# Sheet1.net
KiCad netlist of a schematic drawn in Altium Designer
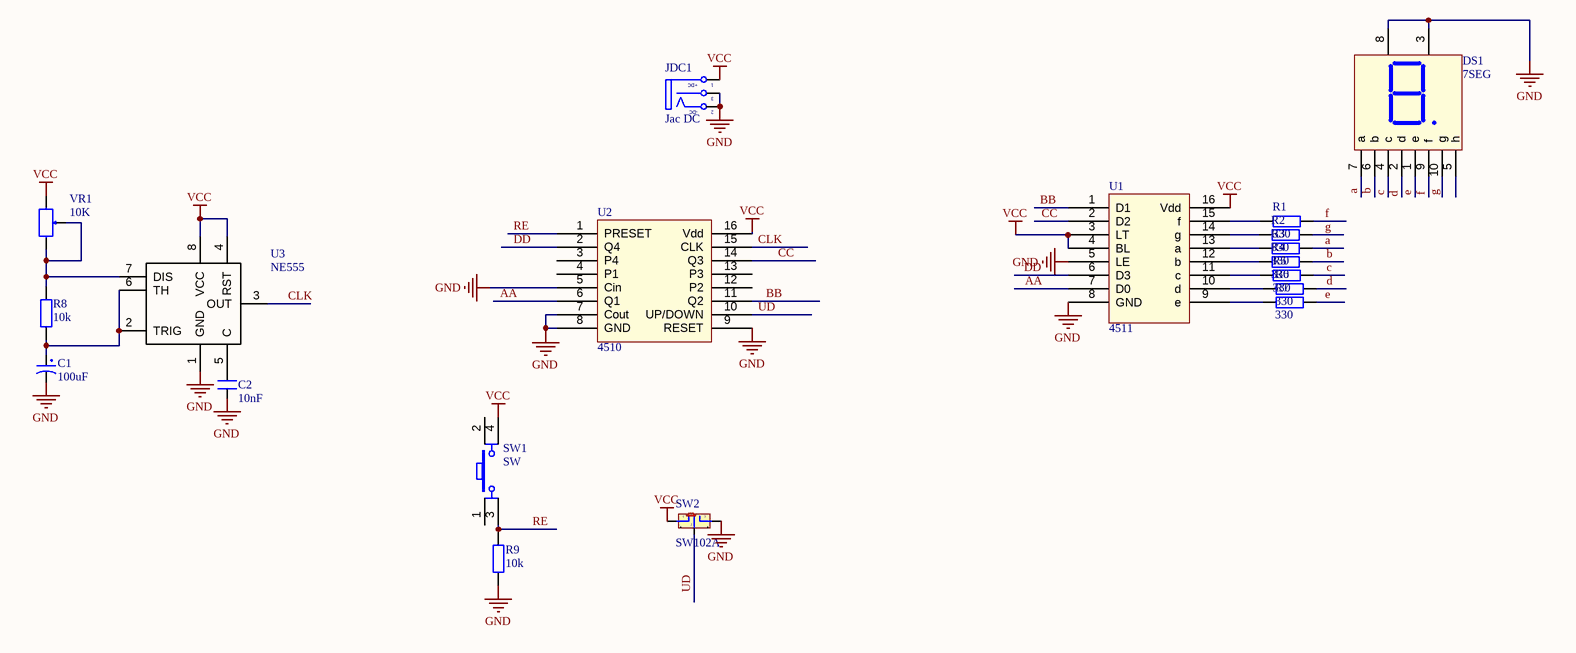
[diagram p0: Sheet1.SchDoc]

(export (version "E")
  (design (tool "Eeschema 10.0.6"))
  (components
    (comp (ref "C1")
      (value "100uF")
      (footprint "CP1/2")
      (description "Cap P  0,1uF < 22uF , 16 - 50V")
      (libsource (lib "syhaunguyen") (part "CP1"))
    )
    (comp (ref "C2")
      (value "10nF")
      (footprint "CN1")
      (description "Cap np  1pF - 472pF")
      (libsource (lib "syhaunguyen") (part "CN1"))
    )
    (comp (ref "DS1")
      (value "7SEG")
      (footprint "LED7SEG-1-0.56")
      (description "14.2 mm General Purpose Blue 7-Segment Display: CC, RH DP, Gray Surface")
      (fields (field (name "PUBLISHER") "Altium Limited"))
      (libsource (lib "LIBRARY") (part "LED7SEG-1"))
    )
    (comp (ref "JDC1")
      (value "Jac DC")
      (footprint "DC-IN")
      (description "Jac DC input")
      (libsource (lib "syhaunguyen") (part "DCIN"))
    )
    (comp (ref "R1")
      (value "330")
      (footprint "R1/4W")
      (description "Resistor 1/4W")
      (libsource (lib "syhaunguyen") (part "R1/4W"))
    )
    (comp (ref "R2")
      (value "330")
      (footprint "R1/4W")
      (description "Resistor 1/4W")
      (libsource (lib "syhaunguyen") (part "R1/4W"))
    )
    (comp (ref "R3")
      (value "330")
      (footprint "R1/4W")
      (description "Resistor 1/4W")
      (libsource (lib "syhaunguyen") (part "R1/4W"))
    )
    (comp (ref "R4")
      (value "330")
      (footprint "R1/4W")
      (description "Resistor 1/4W")
      (libsource (lib "syhaunguyen") (part "R1/4W"))
    )
    (comp (ref "R5")
      (value "330")
      (footprint "R1/4W")
      (description "Resistor 1/4W")
      (libsource (lib "syhaunguyen") (part "R1/4W"))
    )
    (comp (ref "R6")
      (value "330")
      (footprint "R1/4W")
      (description "Resistor 1/4W")
      (libsource (lib "syhaunguyen") (part "R1/4W"))
    )
    (comp (ref "R7")
      (value "330")
      (footprint "R1/4W")
      (description "Resistor 1/4W")
      (libsource (lib "syhaunguyen") (part "R1/4W"))
    )
    (comp (ref "R8")
      (value "10k")
      (footprint "R1/4W")
      (description "Resistor 1/4W")
      (libsource (lib "syhaunguyen") (part "R1/4W"))
    )
    (comp (ref "R9")
      (value "10k")
      (footprint "R1/4W")
      (description "Resistor 1/4W")
      (libsource (lib "syhaunguyen") (part "R1/4W"))
    )
    (comp (ref "SW1")
      (value "SW")
      (footprint "SW4")
      (description "Switch button 4 pin")
      (libsource (lib "syhaunguyen") (part "SW4"))
    )
    (comp (ref "SW2")
      (value "SW102A")
      (footprint "SW102")
      (description "Switch 102 on Broad")
      (libsource (lib "LIBRARY") (part "SW102A"))
    )
    (comp (ref "U1") (value "4511") (footprint "DIP 16") (libsource (lib "thu vien") (part "4511")))
    (comp (ref "U2") (value "4510") (footprint "DIP 16") (libsource (lib "thu vien") (part "4510")))
    (comp (ref "U3")
      (value "NE555")
      (footprint "DIP8")
      (description "TIMER IC")
      (fields
        (field (name "MANUFACTURER PART NUMBER") "NE555DT")
        (field (name "MANUFACTURER") "STMicroelectronics")
      )
      (libsource (lib "MD") (part "NE555"))
    )
    (comp (ref "VR1")
      (value "10K")
      (footprint "VR")
      (description "Var Resistor")
      (libsource (lib "syhaunguyen") (part "VR"))
    )
  )
  (nets
    (net (code "1") (name "/AA") (class "Default")
      (node (ref "U1") (pin "7") (pinfunction "D0_7") (pintype "passive"))
      (node (ref "U2") (pin "6") (pinfunction "Q1_6") (pintype "passive"))
    )
    (net (code "2") (name "/BB") (class "Default")
      (node (ref "U1") (pin "1") (pinfunction "D1_1") (pintype "passive"))
      (node (ref "U2") (pin "11") (pinfunction "Q2_11") (pintype "passive"))
    )
    (net (code "3") (name "/CC") (class "Default")
      (node (ref "U1") (pin "2") (pinfunction "D2_2") (pintype "passive"))
      (node (ref "U2") (pin "14") (pinfunction "Q3_14") (pintype "passive"))
    )
    (net (code "4") (name "/CLK") (class "Default")
      (node (ref "U2") (pin "15") (pinfunction "CLK_15") (pintype "passive"))
      (node (ref "U3") (pin "3") (pinfunction "OUT_3") (pintype "passive"))
    )
    (net (code "5") (name "/DD") (class "Default")
      (node (ref "U1") (pin "6") (pinfunction "D3_6") (pintype "passive"))
      (node (ref "U2") (pin "2") (pinfunction "Q4_2") (pintype "passive"))
    )
    (net (code "6") (name "/RE") (class "Default")
      (node (ref "R9") (pin "2") (pinfunction "2_2") (pintype "passive"))
      (node (ref "SW1") (pin "3") (pintype "passive"))
      (node (ref "U2") (pin "1") (pinfunction "PRESET_1") (pintype "passive"))
    )
    (net (code "7") (name "/UD") (class "Default")
      (node (ref "SW2") (pin "2") (pinfunction "2_2") (pintype "passive"))
      (node (ref "U2") (pin "10") (pinfunction "UP/DOWN_10") (pintype "passive"))
    )
    (net (code "8") (name "/a") (class "Default")
      (node (ref "DS1") (pin "7") (pinfunction "a_7") (pintype "passive"))
      (node (ref "R3") (pin "2") (pinfunction "2_2") (pintype "passive"))
    )
    (net (code "9") (name "/b") (class "Default")
      (node (ref "DS1") (pin "6") (pinfunction "b_6") (pintype "passive"))
      (node (ref "R4") (pin "2") (pinfunction "2_2") (pintype "passive"))
    )
    (net (code "10") (name "/c") (class "Default")
      (node (ref "DS1") (pin "4") (pinfunction "c_4") (pintype "passive"))
      (node (ref "R5") (pin "2") (pinfunction "2_2") (pintype "passive"))
    )
    (net (code "11") (name "/d") (class "Default")
      (node (ref "DS1") (pin "2") (pinfunction "d_2") (pintype "passive"))
      (node (ref "R6") (pin "2") (pinfunction "2_2") (pintype "passive"))
    )
    (net (code "12") (name "/e") (class "Default")
      (node (ref "DS1") (pin "1") (pinfunction "e_1") (pintype "passive"))
      (node (ref "R7") (pin "2") (pinfunction "2_2") (pintype "passive"))
    )
    (net (code "13") (name "/f") (class "Default")
      (node (ref "DS1") (pin "9") (pinfunction "f_9") (pintype "passive"))
      (node (ref "R1") (pin "2") (pinfunction "2_2") (pintype "passive"))
    )
    (net (code "14") (name "/g") (class "Default")
      (node (ref "DS1") (pin "10") (pinfunction "g_10") (pintype "passive"))
      (node (ref "R2") (pin "2") (pinfunction "2_2") (pintype "passive"))
    )
    (net (code "15") (name "GND") (class "Default")
      (node (ref "C1") (pin "2") (pinfunction "2_2") (pintype "passive"))
      (node (ref "C2") (pin "1") (pinfunction "1_1") (pintype "passive"))
      (node (ref "DS1") (pin "3") (pinfunction "Vcc_3") (pintype "passive"))
      (node (ref "DS1") (pin "8") (pinfunction "Vcc_8") (pintype "passive"))
      (node (ref "JDC1") (pin "2") (pinfunction "TN_2") (pintype "passive"))
      (node (ref "JDC1") (pin "3") (pinfunction "S_3") (pintype "power_in"))
      (node (ref "R9") (pin "1") (pinfunction "1_1") (pintype "passive"))
      (node (ref "SW2") (pin "3") (pinfunction "3_3") (pintype "passive"))
      (node (ref "U1") (pin "5") (pinfunction "LE_5") (pintype "passive"))
      (node (ref "U1") (pin "8") (pinfunction "GND_8") (pintype "passive"))
      (node (ref "U2") (pin "5") (pinfunction "Cin_5") (pintype "passive"))
      (node (ref "U2") (pin "7") (pinfunction "Cout_7") (pintype "passive"))
      (node (ref "U2") (pin "8") (pinfunction "GND_8") (pintype "passive"))
      (node (ref "U2") (pin "9") (pinfunction "RESET_9") (pintype "passive"))
      (node (ref "U3") (pin "1") (pinfunction "GND_1") (pintype "passive"))
    )
    (net (code "16") (name "Net-(U1-a)") (class "Default")
      (node (ref "R3") (pin "1") (pinfunction "1_1") (pintype "passive"))
      (node (ref "U1") (pin "13") (pinfunction "a_13") (pintype "passive"))
    )
    (net (code "17") (name "Net-(U1-b)") (class "Default")
      (node (ref "R4") (pin "1") (pinfunction "1_1") (pintype "passive"))
      (node (ref "U1") (pin "12") (pinfunction "b_12") (pintype "passive"))
    )
    (net (code "18") (name "Net-(U1-c)") (class "Default")
      (node (ref "R5") (pin "1") (pinfunction "1_1") (pintype "passive"))
      (node (ref "U1") (pin "11") (pinfunction "c_11") (pintype "passive"))
    )
    (net (code "19") (name "Net-(U1-d)") (class "Default")
      (node (ref "R6") (pin "1") (pinfunction "1_1") (pintype "passive"))
      (node (ref "U1") (pin "10") (pinfunction "d_10") (pintype "passive"))
    )
    (net (code "20") (name "Net-(U1-e)") (class "Default")
      (node (ref "R7") (pin "1") (pinfunction "1_1") (pintype "passive"))
      (node (ref "U1") (pin "9") (pinfunction "e_9") (pintype "passive"))
    )
    (net (code "21") (name "Net-(U1-f)") (class "Default")
      (node (ref "R1") (pin "1") (pinfunction "1_1") (pintype "passive"))
      (node (ref "U1") (pin "15") (pinfunction "f_15") (pintype "passive"))
    )
    (net (code "22") (name "Net-(U1-g)") (class "Default")
      (node (ref "R2") (pin "1") (pinfunction "1_1") (pintype "passive"))
      (node (ref "U1") (pin "14") (pinfunction "g_14") (pintype "passive"))
    )
    (net (code "23") (name "Net-(U3-C)") (class "Default")
      (node (ref "C2") (pin "2") (pinfunction "2_2") (pintype "passive"))
      (node (ref "U3") (pin "5") (pinfunction "C_5") (pintype "passive"))
    )
    (net (code "24") (name "Net-(U3-DIS)") (class "Default")
      (node (ref "R8") (pin "2") (pinfunction "2_2") (pintype "passive"))
      (node (ref "U3") (pin "7") (pinfunction "DIS_7") (pintype "passive"))
      (node (ref "VR1") (pin "2") (pinfunction "2_2") (pintype "passive"))
      (node (ref "VR1") (pin "3") (pinfunction "3_3") (pintype "passive"))
    )
    (net (code "25") (name "Net-(U3-TH)") (class "Default")
      (node (ref "C1") (pin "1") (pinfunction "1_1") (pintype "passive"))
      (node (ref "R8") (pin "1") (pinfunction "1_1") (pintype "passive"))
      (node (ref "U3") (pin "2") (pinfunction "TRIG_2") (pintype "passive"))
      (node (ref "U3") (pin "6") (pinfunction "TH_6") (pintype "passive"))
    )
    (net (code "26") (name "VCC") (class "Default")
      (node (ref "JDC1") (pin "1") (pinfunction "T_1") (pintype "passive"))
      (node (ref "SW1") (pin "4") (pintype "passive"))
      (node (ref "SW2") (pin "1") (pinfunction "1_1") (pintype "passive"))
      (node (ref "U1") (pin "16") (pinfunction "Vdd_16") (pintype "passive"))
      (node (ref "U1") (pin "3") (pinfunction "LT_3") (pintype "passive"))
      (node (ref "U1") (pin "4") (pinfunction "BL_4") (pintype "passive"))
      (node (ref "U2") (pin "16") (pinfunction "Vdd_16") (pintype "passive"))
      (node (ref "U3") (pin "4") (pinfunction "RST_4") (pintype "passive"))
      (node (ref "U3") (pin "8") (pinfunction "VCC_8") (pintype "passive"))
      (node (ref "VR1") (pin "1") (pinfunction "1_1") (pintype "passive"))
    )
    (net (code "27") (name "unconnected-(DS1-h-Pad5)") (class "Default")
      (node (ref "DS1") (pin "5") (pinfunction "h_5") (pintype "passive"))
    )
    (net (code "28") (name "unconnected-(SW1-Pad1)") (class "Default")
      (node (ref "SW1") (pin "1") (pintype "passive"))
    )
    (net (code "29") (name "unconnected-(SW1-Pad2)") (class "Default")
      (node (ref "SW1") (pin "2") (pintype "passive"))
    )
    (net (code "30") (name "unconnected-(SW2-Pad4)") (class "Default")
      (node (ref "SW2") (pin "4") (pinfunction "4_4") (pintype "passive"))
    )
    (net (code "31") (name "unconnected-(SW2-Pad5)") (class "Default")
      (node (ref "SW2") (pin "5") (pinfunction "5_5") (pintype "passive"))
    )
    (net (code "32") (name "unconnected-(U2-P1-Pad4)") (class "Default")
      (node (ref "U2") (pin "4") (pinfunction "P1_4") (pintype "passive"))
    )
    (net (code "33") (name "unconnected-(U2-P2-Pad12)") (class "Default")
      (node (ref "U2") (pin "12") (pinfunction "P2_12") (pintype "passive"))
    )
    (net (code "34") (name "unconnected-(U2-P3-Pad13)") (class "Default")
      (node (ref "U2") (pin "13") (pinfunction "P3_13") (pintype "passive"))
    )
    (net (code "35") (name "unconnected-(U2-P4-Pad3)") (class "Default")
      (node (ref "U2") (pin "3") (pinfunction "P4_3") (pintype "passive"))
    )
  )
)
